# Slave_SX1278.net
KiCad netlist of a schematic drawn in Altium Designer
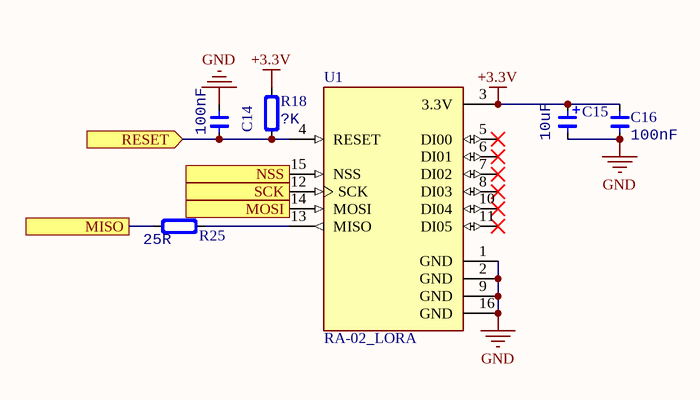
[diagram p0: [Slave]SX1278.SchDoc]

(export (version "E")
  (design (tool "Eeschema 10.0.6"))
  (components
    (comp (ref "C14")
      (value "100nF")
      (footprint "CAP-0603")
      (description "Capacitor")
      (fields (field (name "Comment") "Cap_0603"))
      (libsource (lib "Integrated_Library") (part "Cap_0603"))
    )
    (comp (ref "C15")
      (value "10uF")
      (footprint "CAP_TAN_1206")
      (description "Capacitor Tantalum")
      (fields (field (name "Comment") "C1206"))
      (libsource (lib "Integrated_Library") (part "Cap_Tan_1206"))
    )
    (comp (ref "C16")
      (value "100nF")
      (footprint "CAP-0603")
      (description "Capacitor")
      (fields (field (name "Comment") "Cap_0603"))
      (libsource (lib "") (part "Cap_0603_1"))
    )
    (comp (ref "R18")
      (value "?K")
      (footprint "RES-0805")
      (description "Resistor")
      (fields (field (name "Comment") "R0805"))
      (libsource (lib "Integrated_Library") (part "Res_0805"))
    )
    (comp (ref "R25")
      (value "25R")
      (footprint "RES-0805")
      (description "Resistor")
      (fields (field (name "Comment") "Res_0805"))
      (libsource (lib "Integrated_Library") (part "Res_0805"))
    )
    (comp (ref "U1")
      (value "RA-02_LORA")
      (footprint "MODULE_RA-02_LORA")
      (description "Ra-02 LoRa RF M5Stack Platform Evaluation Expansion Board")
      (fields (field (name "MP") "Ra-02 LoRa") (field (name "MF") "AI-Thinker"))
      (libsource (lib "Integrated_Library") (part "RA-02_LORA"))
    )
  )
  (nets
    (net (code "1") (name "+3.3V") (class "Default")
      (node (ref "C15") (pin "1") (pinfunction "1_1") (pintype "passive"))
      (node (ref "C16") (pin "2") (pinfunction "2_2") (pintype "passive"))
      (node (ref "R18") (pin "2") (pinfunction "2_2") (pintype "passive"))
      (node (ref "U1") (pin "3") (pinfunction "3.3V_3") (pintype "power_in"))
    )
    (net (code "2") (name "/MISO") (class "Default")
      (node (ref "R25") (pin "1") (pinfunction "1_1") (pintype "passive"))
    )
    (net (code "3") (name "/MOSI") (class "Default")
      (node (ref "U1") (pin "14") (pinfunction "MOSI_14") (pintype "input"))
    )
    (net (code "4") (name "/NSS") (class "Default")
      (node (ref "U1") (pin "15") (pinfunction "NSS_15") (pintype "input"))
    )
    (net (code "5") (name "/RESET") (class "Default")
      (node (ref "C14") (pin "2") (pinfunction "2_2") (pintype "passive"))
      (node (ref "R18") (pin "1") (pinfunction "1_1") (pintype "passive"))
      (node (ref "U1") (pin "4") (pinfunction "RESET_4") (pintype "input"))
    )
    (net (code "6") (name "/SCK") (class "Default")
      (node (ref "U1") (pin "12") (pinfunction "SCK_12") (pintype "input"))
    )
    (net (code "7") (name "GND") (class "Default")
      (node (ref "C14") (pin "1") (pinfunction "1_1") (pintype "passive"))
      (node (ref "C15") (pin "2") (pinfunction "2_2") (pintype "passive"))
      (node (ref "C16") (pin "1") (pinfunction "1_1") (pintype "passive"))
      (node (ref "U1") (pin "1") (pinfunction "GND_1") (pintype "power_in"))
      (node (ref "U1") (pin "16") (pinfunction "GND_16") (pintype "power_in"))
      (node (ref "U1") (pin "2") (pinfunction "GND_2") (pintype "power_in"))
      (node (ref "U1") (pin "9") (pinfunction "GND_9") (pintype "power_in"))
    )
    (net (code "8") (name "Net-(U1-MISO)") (class "Default")
      (node (ref "R25") (pin "2") (pinfunction "2_2") (pintype "passive"))
      (node (ref "U1") (pin "13") (pinfunction "MISO_13") (pintype "output"))
    )
    (net (code "9") (name "unconnected-(U1-DI00-Pad5)") (class "Default")
      (node (ref "U1") (pin "5") (pinfunction "DI00_5") (pintype "bidirectional+no_connect"))
    )
    (net (code "10") (name "unconnected-(U1-DI01-Pad6)") (class "Default")
      (node (ref "U1") (pin "6") (pinfunction "DI01_6") (pintype "bidirectional+no_connect"))
    )
    (net (code "11") (name "unconnected-(U1-DI02-Pad7)") (class "Default")
      (node (ref "U1") (pin "7") (pinfunction "DI02_7") (pintype "bidirectional+no_connect"))
    )
    (net (code "12") (name "unconnected-(U1-DI03-Pad8)") (class "Default")
      (node (ref "U1") (pin "8") (pinfunction "DI03_8") (pintype "bidirectional+no_connect"))
    )
    (net (code "13") (name "unconnected-(U1-DI04-Pad10)") (class "Default")
      (node (ref "U1") (pin "10") (pinfunction "DI04_10") (pintype "bidirectional+no_connect"))
    )
    (net (code "14") (name "unconnected-(U1-DI05-Pad11)") (class "Default")
      (node (ref "U1") (pin "11") (pinfunction "DI05_11") (pintype "bidirectional+no_connect"))
    )
  )
)
